# TestPowerMergeSys.net
KiCad netlist of a schematic drawn in Altium Designer
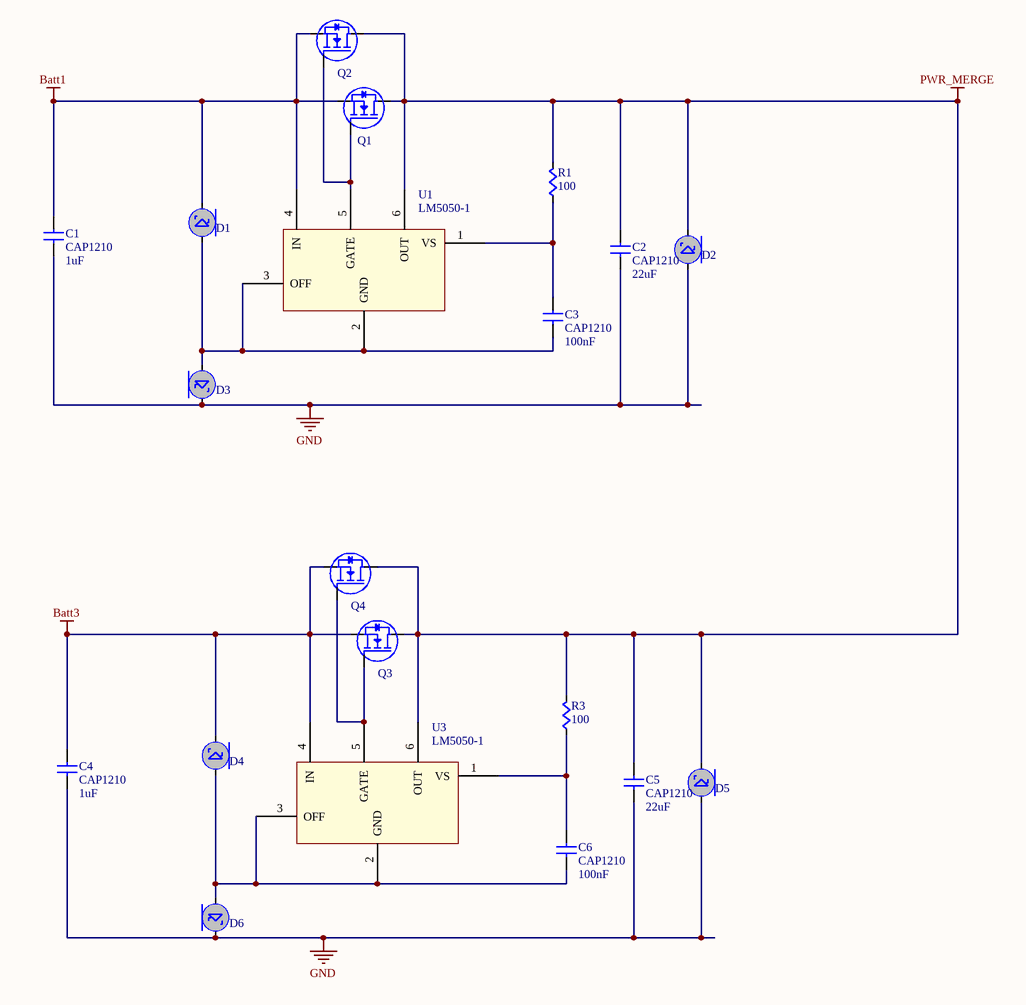
[diagram p0: TestPowerMergeSys.SchDoc]

(export (version "E")
  (design (tool "Eeschema 10.0.6"))
  (components
    (comp (ref "C1")
      (value "CAP1210")
      (footprint "CAP1210")
      (description "CAP CER 10UF 50V 20% X5R 1210")
      (fields (field (name "ALTIUM_VALUE") "1uF"))
      (libsource (lib "SubjuGator8") (part "CAP1210"))
    )
    (comp (ref "C2")
      (value "CAP1210")
      (footprint "CAP1210")
      (description "CAP CER 10UF 50V 20% X5R 1210")
      (fields (field (name "ALTIUM_VALUE") "22uF"))
      (libsource (lib "SubjuGator8") (part "CAP1210"))
    )
    (comp (ref "C3")
      (value "CAP1210")
      (footprint "CAP1210")
      (description "CAP CER 10UF 50V 20% X5R 1210")
      (fields (field (name "ALTIUM_VALUE") "100nF"))
      (libsource (lib "SubjuGator8") (part "CAP1210"))
    )
    (comp (ref "C4")
      (value "CAP1210")
      (footprint "CAP1210")
      (description "CAP CER 1UF 50V 20% X5R 1210")
      (fields (field (name "ALTIUM_VALUE") "1uF"))
      (libsource (lib "SubjuGator8") (part "CAP1210"))
    )
    (comp (ref "C5")
      (value "CAP1210")
      (footprint "CAP1210")
      (description "CAP CER 10UF 50V 20% X5R 1210")
      (fields (field (name "ALTIUM_VALUE") "22uF"))
      (libsource (lib "SubjuGator8") (part "CAP1210"))
    )
    (comp (ref "C6")
      (value "CAP1210")
      (footprint "CAP1210")
      (description "CAP CER 10UF 50V 20% X5R 1210")
      (fields (field (name "ALTIUM_VALUE") "100nF"))
      (libsource (lib "SubjuGator8") (part "CAP1210"))
    )
    (comp (ref "D1")
      (value "SS16T3G")
      (footprint "SS16T3G")
      (description "DIODE SCHOTTKY 60V 1A SMA")
      (libsource (lib "SubjuGator8") (part "SS16T3G"))
    )
    (comp (ref "D2")
      (value "SMBJ60A-13-F")
      (footprint "SMBJ60A-13-F")
      (description "TVS UNIDIRECT 600W 60V SMB")
      (libsource (lib "SubjuGator8") (part "SMBJ60A-13-F"))
    )
    (comp (ref "D3")
      (value "SS16T3G")
      (footprint "SS16T3G")
      (description "DIODE SCHOTTKY 60V 1A SMA")
      (libsource (lib "") (part "SS16T3G_1"))
    )
    (comp (ref "D4")
      (value "SS16T3G")
      (footprint "SS16T3G")
      (description "DIODE SCHOTTKY 60V 1A SMA")
      (libsource (lib "SubjuGator8") (part "SS16T3G"))
    )
    (comp (ref "D5")
      (value "SMBJ60A-13-F")
      (footprint "SMBJ60A-13-F")
      (description "TVS UNIDIRECT 600W 60V SMB")
      (libsource (lib "SubjuGator8") (part "SMBJ60A-13-F"))
    )
    (comp (ref "D6")
      (value "SS16T3G")
      (footprint "SS16T3G")
      (description "DIODE SCHOTTKY 60V 1A SMA")
      (libsource (lib "") (part "SS16T3G_1"))
    )
    (comp (ref "Q1")
      (value "IRLR3636TRPBF‎")
      (footprint "TO-220AB Heatsink")
      (description "HEXFET Power MOSFET")
      (libsource (lib "SubjuGator8") (part "IRFx3306PbF"))
    )
    (comp (ref "Q2")
      (value "IRLR3636TRPBF‎")
      (footprint "TO-220AB Heatsink")
      (description "HEXFET Power MOSFET")
      (libsource (lib "SubjuGator8") (part "IRFx3306PbF"))
    )
    (comp (ref "Q3")
      (value "IRLR3636TRPBF‎")
      (footprint "TO-220AB Heatsink")
      (description "HEXFET Power MOSFET")
      (libsource (lib "SubjuGator8") (part "IRFx3306PbF"))
    )
    (comp (ref "Q4")
      (value "IRLR3636TRPBF‎")
      (footprint "TO-220AB Heatsink")
      (description "HEXFET Power MOSFET")
      (libsource (lib "SubjuGator8") (part "IRFx3306PbF"))
    )
    (comp (ref "R1")
      (value "100")
      (footprint "RES0603")
      (fields (field (name "Comment") "Res"))
      (libsource (lib "SubjuGator8") (part "Res"))
    )
    (comp (ref "R3")
      (value "100")
      (footprint "RES0603")
      (description "100 Ohm 0603 Resistor")
      (fields (field (name "Comment") "Res"))
      (libsource (lib "SubjuGator8") (part "Res"))
    )
    (comp (ref "U1")
      (value "LM5050-1")
      (footprint "LM5050")
      (description "High-Side OR-ing FET Controller")
      (libsource (lib "SubjuGator8") (part "LM5050"))
    )
    (comp (ref "U3")
      (value "LM5050-1")
      (footprint "LM5050")
      (description "High-Side OR-ing FET Controller")
      (libsource (lib "SubjuGator8") (part "LM5050"))
    )
  )
  (nets
    (net (code "1") (name "Batt1") (class "Default")
      (node (ref "C1") (pin "1") (pinfunction "A_1") (pintype "passive"))
      (node (ref "D1") (pin "C") (pinfunction "C_C") (pintype "passive"))
      (node (ref "Q1") (pin "S") (pinfunction "S_S") (pintype "passive"))
      (node (ref "Q2") (pin "S") (pinfunction "S_S") (pintype "passive"))
      (node (ref "U1") (pin "4") (pinfunction "IN_4") (pintype "passive"))
    )
    (net (code "2") (name "Batt3") (class "Default")
      (node (ref "C4") (pin "1") (pinfunction "A_1") (pintype "passive"))
      (node (ref "D4") (pin "C") (pinfunction "C_C") (pintype "passive"))
      (node (ref "Q3") (pin "S") (pinfunction "S_S") (pintype "passive"))
      (node (ref "Q4") (pin "S") (pinfunction "S_S") (pintype "passive"))
      (node (ref "U3") (pin "4") (pinfunction "IN_4") (pintype "passive"))
    )
    (net (code "3") (name "GND") (class "Default")
      (node (ref "C1") (pin "2") (pinfunction "B_2") (pintype "passive"))
      (node (ref "C2") (pin "2") (pinfunction "B_2") (pintype "passive"))
      (node (ref "C4") (pin "2") (pinfunction "B_2") (pintype "passive"))
      (node (ref "C5") (pin "2") (pinfunction "B_2") (pintype "passive"))
      (node (ref "D2") (pin "A") (pinfunction "A_A") (pintype "passive"))
      (node (ref "D3") (pin "C") (pinfunction "C_C") (pintype "passive"))
      (node (ref "D5") (pin "A") (pinfunction "A_A") (pintype "passive"))
      (node (ref "D6") (pin "C") (pinfunction "C_C") (pintype "passive"))
    )
    (net (code "4") (name "Net-(C3-A)") (class "Default")
      (node (ref "C3") (pin "1") (pinfunction "A_1") (pintype "passive"))
      (node (ref "R1") (pin "2") (pinfunction "B_2") (pintype "passive"))
      (node (ref "U1") (pin "1") (pinfunction "VS_1") (pintype "passive"))
    )
    (net (code "5") (name "Net-(C3-B)") (class "Default")
      (node (ref "C3") (pin "2") (pinfunction "B_2") (pintype "passive"))
      (node (ref "D1") (pin "A") (pinfunction "A_A") (pintype "passive"))
      (node (ref "D3") (pin "A") (pinfunction "A_A") (pintype "passive"))
      (node (ref "U1") (pin "2") (pinfunction "GND_2") (pintype "passive"))
      (node (ref "U1") (pin "3") (pinfunction "OFF_3") (pintype "passive"))
    )
    (net (code "6") (name "Net-(C6-A)") (class "Default")
      (node (ref "C6") (pin "1") (pinfunction "A_1") (pintype "passive"))
      (node (ref "R3") (pin "2") (pinfunction "B_2") (pintype "passive"))
      (node (ref "U3") (pin "1") (pinfunction "VS_1") (pintype "passive"))
    )
    (net (code "7") (name "Net-(C6-B)") (class "Default")
      (node (ref "C6") (pin "2") (pinfunction "B_2") (pintype "passive"))
      (node (ref "D4") (pin "A") (pinfunction "A_A") (pintype "passive"))
      (node (ref "D6") (pin "A") (pinfunction "A_A") (pintype "passive"))
      (node (ref "U3") (pin "2") (pinfunction "GND_2") (pintype "passive"))
      (node (ref "U3") (pin "3") (pinfunction "OFF_3") (pintype "passive"))
    )
    (net (code "8") (name "Net-(U1-GATE)") (class "Default")
      (node (ref "Q1") (pin "G") (pinfunction "G_G") (pintype "passive"))
      (node (ref "Q2") (pin "G") (pinfunction "G_G") (pintype "passive"))
      (node (ref "U1") (pin "5") (pinfunction "GATE_5") (pintype "passive"))
    )
    (net (code "9") (name "Net-(U3-GATE)") (class "Default")
      (node (ref "Q3") (pin "G") (pinfunction "G_G") (pintype "passive"))
      (node (ref "Q4") (pin "G") (pinfunction "G_G") (pintype "passive"))
      (node (ref "U3") (pin "5") (pinfunction "GATE_5") (pintype "passive"))
    )
    (net (code "10") (name "PWR_MERGE") (class "Default")
      (node (ref "C2") (pin "1") (pinfunction "A_1") (pintype "passive"))
      (node (ref "C5") (pin "1") (pinfunction "A_1") (pintype "passive"))
      (node (ref "D2") (pin "C") (pinfunction "C_C") (pintype "passive"))
      (node (ref "D5") (pin "C") (pinfunction "C_C") (pintype "passive"))
      (node (ref "Q1") (pin "D") (pinfunction "D_D") (pintype "passive"))
      (node (ref "Q2") (pin "D") (pinfunction "D_D") (pintype "passive"))
      (node (ref "Q3") (pin "D") (pinfunction "D_D") (pintype "passive"))
      (node (ref "Q4") (pin "D") (pinfunction "D_D") (pintype "passive"))
      (node (ref "R1") (pin "1") (pinfunction "A_1") (pintype "passive"))
      (node (ref "R3") (pin "1") (pinfunction "A_1") (pintype "passive"))
      (node (ref "U1") (pin "6") (pinfunction "OUT_6") (pintype "passive"))
      (node (ref "U3") (pin "6") (pinfunction "OUT_6") (pintype "passive"))
    )
  )
)
